# hw2.net
KiCad netlist of a schematic drawn in EAGLE
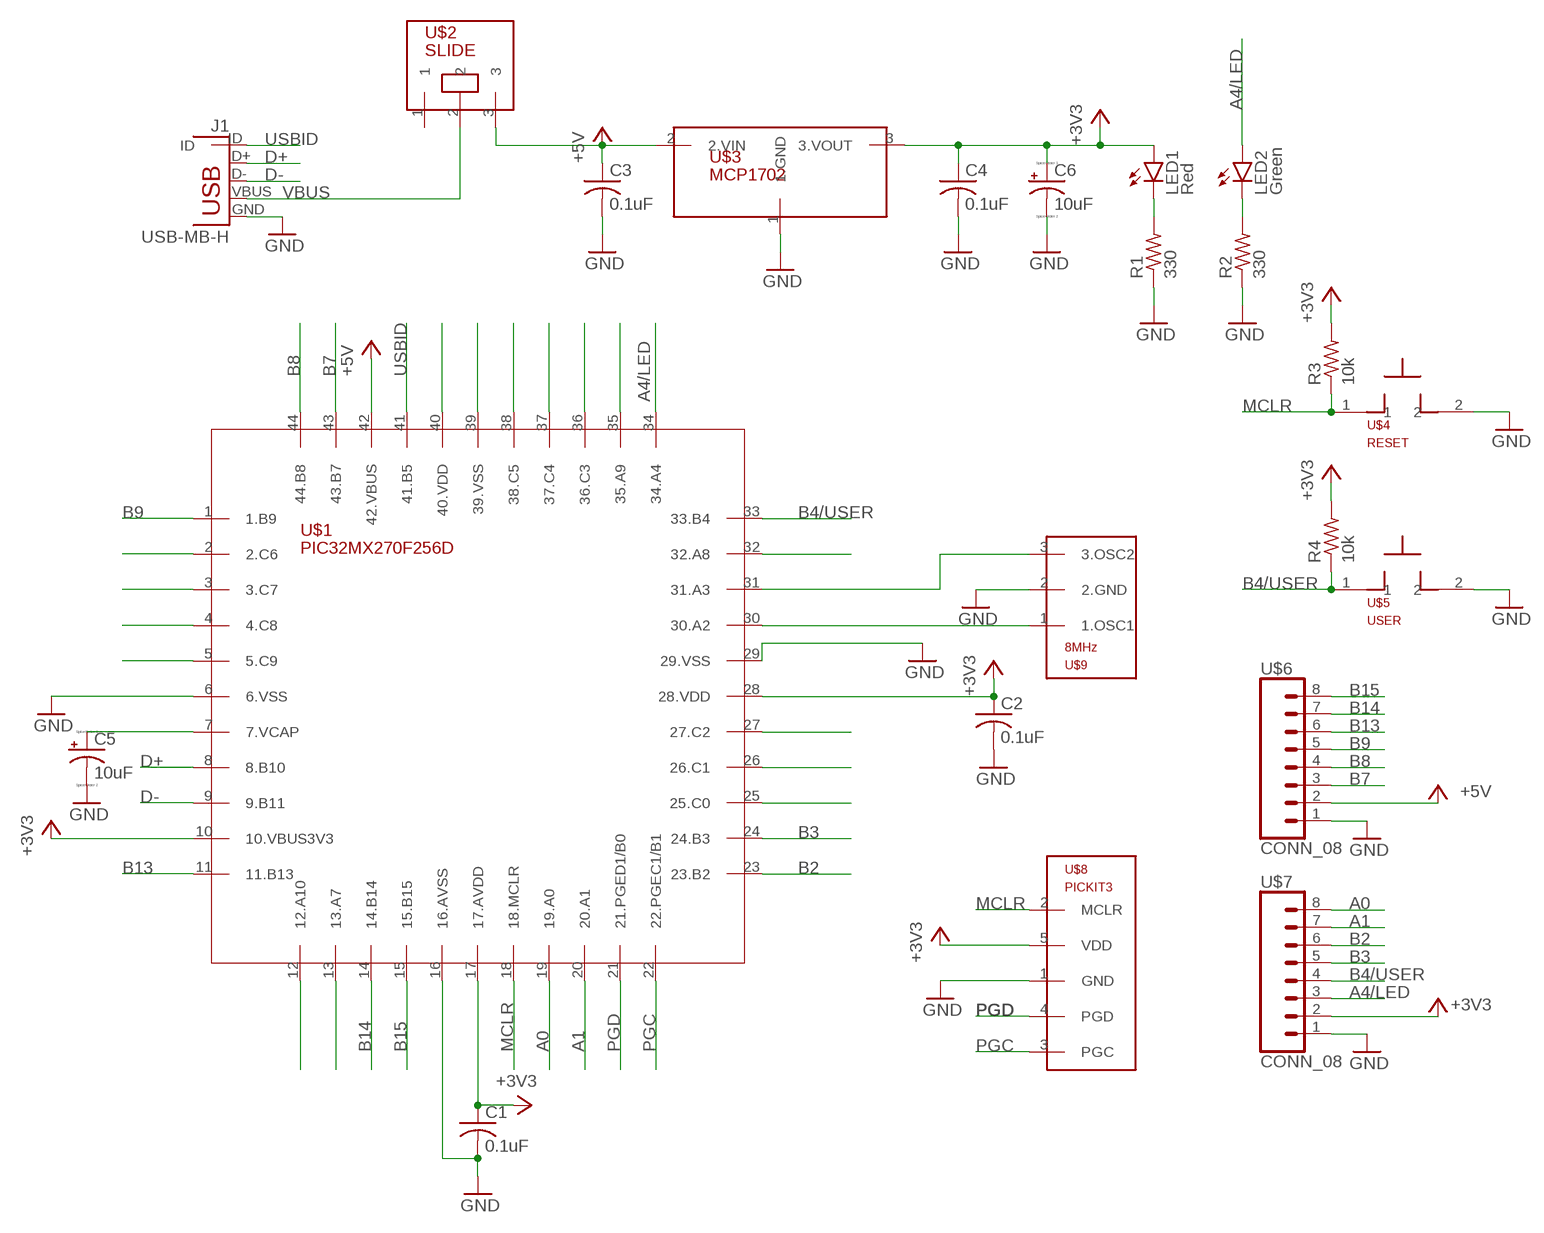
[diagram p0: schematic, sheet 1]

(export (version "E")
  (design (tool "Eeschema 10.0.6"))
  (components
    (comp (ref "C1")
      (value "0.1uF")
      (footprint "eagle-import:C025-025X050")
      (libsource (lib "eagle-import") (part "C-US025-025X050"))
    )
    (comp (ref "C2")
      (value "0.1uF")
      (footprint "eagle-import:C025-025X050")
      (libsource (lib "eagle-import") (part "C-US025-025X050"))
    )
    (comp (ref "C3")
      (value "0.1uF")
      (footprint "eagle-import:C025-025X050")
      (libsource (lib "eagle-import") (part "C-US025-025X050"))
    )
    (comp (ref "C4")
      (value "0.1uF")
      (footprint "eagle-import:C025-025X050")
      (libsource (lib "eagle-import") (part "C-US025-025X050"))
    )
    (comp (ref "C5")
      (value "10uF")
      (footprint "eagle-import:B45181B")
      (libsource (lib "eagle-import") (part "CPOL-USB45181B"))
    )
    (comp (ref "C6")
      (value "10uF")
      (footprint "eagle-import:B45181B")
      (libsource (lib "eagle-import") (part "CPOL-USB45181B"))
    )
    (comp (ref "J1")
      (value "USB-MB-H")
      (footprint "eagle-import:USB-MB-H")
      (libsource (lib "eagle-import") (part "USB-MB-H"))
    )
    (comp (ref "LED1")
      (value "Red")
      (footprint "eagle-import:LED3MM")
      (libsource (lib "eagle-import") (part "LED3MM"))
    )
    (comp (ref "LED2")
      (value "Green")
      (footprint "eagle-import:LED3MM")
      (libsource (lib "eagle-import") (part "LED3MM"))
    )
    (comp (ref "R1")
      (value "330")
      (footprint "eagle-import:0207_10")
      (libsource (lib "eagle-import") (part "R-US_0207/10"))
    )
    (comp (ref "R2")
      (value "330")
      (footprint "eagle-import:0207_10")
      (libsource (lib "eagle-import") (part "R-US_0207/10"))
    )
    (comp (ref "R3")
      (value "10k")
      (footprint "eagle-import:0207_10")
      (libsource (lib "eagle-import") (part "R-US_0207/10"))
    )
    (comp (ref "R4")
      (value "10k")
      (footprint "eagle-import:0207_10")
      (libsource (lib "eagle-import") (part "R-US_0207/10"))
    )
    (comp (ref "U$1")
      (value "PIC32MX270F256D")
      (footprint "eagle-import:TQFP44")
      (libsource (lib "eagle-import") (part "PIC32MX270F256D"))
    )
    (comp (ref "U$2")
      (value "SLIDE")
      (footprint "eagle-import:SLIDE")
      (libsource (lib "eagle-import") (part "SLIDE"))
    )
    (comp (ref "U$3")
      (value "MCP1702")
      (footprint "eagle-import:TO92")
      (libsource (lib "eagle-import") (part "MCP1702"))
    )
    (comp (ref "U$4")
      (value "RESET")
      (footprint "eagle-import:PB")
      (libsource (lib "eagle-import") (part "PB"))
    )
    (comp (ref "U$5")
      (value "USER")
      (footprint "eagle-import:PB")
      (libsource (lib "eagle-import") (part "PB"))
    )
    (comp (ref "U$6")
      (value "CONN_08")
      (footprint "eagle-import:1X08")
      (libsource (lib "eagle-import") (part "CONN_08"))
    )
    (comp (ref "U$7")
      (value "CONN_08")
      (footprint "eagle-import:1X08")
      (libsource (lib "eagle-import") (part "CONN_08"))
    )
    (comp (ref "U$8")
      (value "PICKIT3")
      (footprint "eagle-import:1X05")
      (libsource (lib "eagle-import") (part "PICKIT3"))
    )
    (comp (ref "U$9")
      (value "8MHz")
      (footprint "eagle-import:OSC")
      (libsource (lib "eagle-import") (part "OSC"))
    )
  )
  (nets
    (net (code "1") (name "+3V3") (class "Default")
      (node (ref "C1") (pin "1") (pinfunction "1_1") (pintype "passive"))
      (node (ref "C2") (pin "1") (pinfunction "1_1") (pintype "passive"))
      (node (ref "C4") (pin "1") (pinfunction "1_1") (pintype "passive"))
      (node (ref "C6") (pin "+") (pinfunction "+_+") (pintype "passive"))
      (node (ref "LED1") (pin "A") (pinfunction "A_A") (pintype "passive"))
      (node (ref "R3") (pin "2") (pinfunction "2_2") (pintype "passive"))
      (node (ref "R4") (pin "2") (pinfunction "2_2") (pintype "passive"))
      (node (ref "U$1") (pin "10") (pinfunction "10.VBUS3V3_10") (pintype "bidirectional"))
      (node (ref "U$1") (pin "17") (pinfunction "17.AVDD_17") (pintype "bidirectional"))
      (node (ref "U$1") (pin "28") (pinfunction "28.VDD_28") (pintype "bidirectional"))
      (node (ref "U$3") (pin "3") (pinfunction "3.VOUT_3") (pintype "bidirectional"))
      (node (ref "U$7") (pin "2") (pinfunction "2_2") (pintype "passive"))
      (node (ref "U$8") (pin "5") (pinfunction "VDD_5") (pintype "bidirectional"))
    )
    (net (code "2") (name "+5V") (class "Default")
      (node (ref "C3") (pin "1") (pinfunction "1_1") (pintype "passive"))
      (node (ref "U$1") (pin "42") (pinfunction "42.VBUS_42") (pintype "bidirectional"))
      (node (ref "U$2") (pin "3") (pinfunction "3_3") (pintype "bidirectional"))
      (node (ref "U$3") (pin "2") (pinfunction "2.VIN_2") (pintype "bidirectional"))
      (node (ref "U$6") (pin "2") (pinfunction "2_2") (pintype "passive"))
    )
    (net (code "3") (name "/A0") (class "Default")
      (node (ref "U$1") (pin "19") (pinfunction "19.A0_19") (pintype "bidirectional"))
      (node (ref "U$7") (pin "8") (pinfunction "8_8") (pintype "passive"))
    )
    (net (code "4") (name "/A1") (class "Default")
      (node (ref "U$1") (pin "20") (pinfunction "20.A1_20") (pintype "bidirectional"))
      (node (ref "U$7") (pin "7") (pinfunction "7_7") (pintype "passive"))
    )
    (net (code "5") (name "/A4{slash}LED") (class "Default")
      (node (ref "LED2") (pin "A") (pinfunction "A_A") (pintype "passive"))
      (node (ref "U$1") (pin "34") (pinfunction "34.A4_34") (pintype "bidirectional"))
      (node (ref "U$7") (pin "3") (pinfunction "3_3") (pintype "passive"))
    )
    (net (code "6") (name "/B2") (class "Default")
      (node (ref "U$1") (pin "23") (pinfunction "23.B2_23") (pintype "bidirectional"))
      (node (ref "U$7") (pin "6") (pinfunction "6_6") (pintype "passive"))
    )
    (net (code "7") (name "/B3") (class "Default")
      (node (ref "U$1") (pin "24") (pinfunction "24.B3_24") (pintype "bidirectional"))
      (node (ref "U$7") (pin "5") (pinfunction "5_5") (pintype "passive"))
    )
    (net (code "8") (name "/B4{slash}USER") (class "Default")
      (node (ref "R4") (pin "1") (pinfunction "1_1") (pintype "passive"))
      (node (ref "U$1") (pin "33") (pinfunction "33.B4_33") (pintype "bidirectional"))
      (node (ref "U$5") (pin "1") (pinfunction "1_1") (pintype "bidirectional"))
      (node (ref "U$7") (pin "4") (pinfunction "4_4") (pintype "passive"))
    )
    (net (code "9") (name "/B7") (class "Default")
      (node (ref "U$1") (pin "43") (pinfunction "43.B7_43") (pintype "bidirectional"))
      (node (ref "U$6") (pin "3") (pinfunction "3_3") (pintype "passive"))
    )
    (net (code "10") (name "/B8") (class "Default")
      (node (ref "U$1") (pin "44") (pinfunction "44.B8_44") (pintype "bidirectional"))
      (node (ref "U$6") (pin "4") (pinfunction "4_4") (pintype "passive"))
    )
    (net (code "11") (name "/B9") (class "Default")
      (node (ref "U$1") (pin "1") (pinfunction "1.B9_1") (pintype "bidirectional"))
      (node (ref "U$6") (pin "5") (pinfunction "5_5") (pintype "passive"))
    )
    (net (code "12") (name "/B13") (class "Default")
      (node (ref "U$1") (pin "11") (pinfunction "11.B13_11") (pintype "bidirectional"))
      (node (ref "U$6") (pin "6") (pinfunction "6_6") (pintype "passive"))
    )
    (net (code "13") (name "/B14") (class "Default")
      (node (ref "U$1") (pin "14") (pinfunction "14.B14_14") (pintype "bidirectional"))
      (node (ref "U$6") (pin "7") (pinfunction "7_7") (pintype "passive"))
    )
    (net (code "14") (name "/B15") (class "Default")
      (node (ref "U$1") (pin "15") (pinfunction "15.B15_15") (pintype "bidirectional"))
      (node (ref "U$6") (pin "8") (pinfunction "8_8") (pintype "passive"))
    )
    (net (code "15") (name "/D+") (class "Default")
      (node (ref "J1") (pin "D+") (pinfunction "D+_D+") (pintype "bidirectional"))
      (node (ref "U$1") (pin "8") (pinfunction "8.B10_8") (pintype "bidirectional"))
    )
    (net (code "16") (name "/D-") (class "Default")
      (node (ref "J1") (pin "D-") (pinfunction "D-_D-") (pintype "bidirectional"))
      (node (ref "U$1") (pin "9") (pinfunction "9.B11_9") (pintype "bidirectional"))
    )
    (net (code "17") (name "/MCLR") (class "Default")
      (node (ref "R3") (pin "1") (pinfunction "1_1") (pintype "passive"))
      (node (ref "U$1") (pin "18") (pinfunction "18.MCLR_18") (pintype "bidirectional"))
      (node (ref "U$4") (pin "1") (pinfunction "1_1") (pintype "bidirectional"))
      (node (ref "U$8") (pin "2") (pinfunction "MCLR_2") (pintype "bidirectional"))
    )
    (net (code "18") (name "/PGC") (class "Default")
      (node (ref "U$1") (pin "22") (pinfunction "22.PGEC1/B1_22") (pintype "bidirectional"))
      (node (ref "U$8") (pin "3") (pinfunction "PGC_3") (pintype "bidirectional"))
    )
    (net (code "19") (name "/PGD") (class "Default")
      (node (ref "U$1") (pin "21") (pinfunction "21.PGED1/B0_21") (pintype "bidirectional"))
      (node (ref "U$8") (pin "4") (pinfunction "PGD_4") (pintype "bidirectional"))
    )
    (net (code "20") (name "/USBID") (class "Default")
      (node (ref "J1") (pin "ID") (pinfunction "ID_ID") (pintype "bidirectional"))
      (node (ref "U$1") (pin "41") (pinfunction "41.B5_41") (pintype "bidirectional"))
    )
    (net (code "21") (name "/VBUS") (class "Default")
      (node (ref "J1") (pin "VBUS") (pinfunction "VBUS_VBUS") (pintype "bidirectional"))
      (node (ref "U$2") (pin "2") (pinfunction "2_2") (pintype "bidirectional"))
    )
    (net (code "22") (name "GND") (class "Default")
      (node (ref "C1") (pin "2") (pinfunction "2_2") (pintype "passive"))
      (node (ref "C2") (pin "2") (pinfunction "2_2") (pintype "passive"))
      (node (ref "C3") (pin "2") (pinfunction "2_2") (pintype "passive"))
      (node (ref "C4") (pin "2") (pinfunction "2_2") (pintype "passive"))
      (node (ref "C5") (pin "-") (pinfunction "-_-") (pintype "passive"))
      (node (ref "C6") (pin "-") (pinfunction "-_-") (pintype "passive"))
      (node (ref "J1") (pin "GND") (pinfunction "GND_GND") (pintype "bidirectional"))
      (node (ref "R1") (pin "1") (pinfunction "1_1") (pintype "passive"))
      (node (ref "R2") (pin "1") (pinfunction "1_1") (pintype "passive"))
      (node (ref "U$1") (pin "16") (pinfunction "16.AVSS_16") (pintype "bidirectional"))
      (node (ref "U$1") (pin "29") (pinfunction "29.VSS_29") (pintype "bidirectional"))
      (node (ref "U$1") (pin "6") (pinfunction "6.VSS_6") (pintype "bidirectional"))
      (node (ref "U$3") (pin "1") (pinfunction "1.GND_1") (pintype "bidirectional"))
      (node (ref "U$4") (pin "2") (pinfunction "2_2") (pintype "bidirectional"))
      (node (ref "U$5") (pin "2") (pinfunction "2_2") (pintype "bidirectional"))
      (node (ref "U$6") (pin "1") (pinfunction "1_1") (pintype "passive"))
      (node (ref "U$7") (pin "1") (pinfunction "1_1") (pintype "passive"))
      (node (ref "U$8") (pin "1") (pinfunction "GND_1") (pintype "bidirectional"))
      (node (ref "U$9") (pin "2") (pinfunction "2.GND_2") (pintype "bidirectional"))
    )
    (net (code "23") (name "Net-(LED1-C)") (class "Default")
      (node (ref "LED1") (pin "K") (pinfunction "C_K") (pintype "passive"))
      (node (ref "R1") (pin "2") (pinfunction "2_2") (pintype "passive"))
    )
    (net (code "24") (name "Net-(LED2-C)") (class "Default")
      (node (ref "LED2") (pin "K") (pinfunction "C_K") (pintype "passive"))
      (node (ref "R2") (pin "2") (pinfunction "2_2") (pintype "passive"))
    )
    (net (code "25") (name "Net-(U$1-7.VCAP)") (class "Default")
      (node (ref "C5") (pin "+") (pinfunction "+_+") (pintype "passive"))
      (node (ref "U$1") (pin "7") (pinfunction "7.VCAP_7") (pintype "bidirectional"))
    )
    (net (code "26") (name "Net-(U$1-30.A2)") (class "Default")
      (node (ref "U$1") (pin "30") (pinfunction "30.A2_30") (pintype "bidirectional"))
      (node (ref "U$9") (pin "1") (pinfunction "1.OSC1_1") (pintype "bidirectional"))
    )
    (net (code "27") (name "Net-(U$1-31.A3)") (class "Default")
      (node (ref "U$1") (pin "31") (pinfunction "31.A3_31") (pintype "bidirectional"))
      (node (ref "U$9") (pin "3") (pinfunction "3.OSC2_3") (pintype "bidirectional"))
    )
    (net (code "28") (name "unconnected-(U$1-2.C6-Pad2)") (class "Default")
      (node (ref "U$1") (pin "2") (pinfunction "2.C6_2") (pintype "bidirectional"))
    )
    (net (code "29") (name "unconnected-(U$1-3.C7-Pad3)") (class "Default")
      (node (ref "U$1") (pin "3") (pinfunction "3.C7_3") (pintype "bidirectional"))
    )
    (net (code "30") (name "unconnected-(U$1-4.C8-Pad4)") (class "Default")
      (node (ref "U$1") (pin "4") (pinfunction "4.C8_4") (pintype "bidirectional"))
    )
    (net (code "31") (name "unconnected-(U$1-5.C9-Pad5)") (class "Default")
      (node (ref "U$1") (pin "5") (pinfunction "5.C9_5") (pintype "bidirectional"))
    )
    (net (code "32") (name "unconnected-(U$1-12.A10-Pad12)") (class "Default")
      (node (ref "U$1") (pin "12") (pinfunction "12.A10_12") (pintype "bidirectional"))
    )
    (net (code "33") (name "unconnected-(U$1-13.A7-Pad13)") (class "Default")
      (node (ref "U$1") (pin "13") (pinfunction "13.A7_13") (pintype "bidirectional"))
    )
    (net (code "34") (name "unconnected-(U$1-25.C0-Pad25)") (class "Default")
      (node (ref "U$1") (pin "25") (pinfunction "25.C0_25") (pintype "bidirectional"))
    )
    (net (code "35") (name "unconnected-(U$1-26.C1-Pad26)") (class "Default")
      (node (ref "U$1") (pin "26") (pinfunction "26.C1_26") (pintype "bidirectional"))
    )
    (net (code "36") (name "unconnected-(U$1-27.C2-Pad27)") (class "Default")
      (node (ref "U$1") (pin "27") (pinfunction "27.C2_27") (pintype "bidirectional"))
    )
    (net (code "37") (name "unconnected-(U$1-32.A8-Pad32)") (class "Default")
      (node (ref "U$1") (pin "32") (pinfunction "32.A8_32") (pintype "bidirectional"))
    )
    (net (code "38") (name "unconnected-(U$1-35.A9-Pad35)") (class "Default")
      (node (ref "U$1") (pin "35") (pinfunction "35.A9_35") (pintype "bidirectional"))
    )
    (net (code "39") (name "unconnected-(U$1-36.C3-Pad36)") (class "Default")
      (node (ref "U$1") (pin "36") (pinfunction "36.C3_36") (pintype "bidirectional"))
    )
    (net (code "40") (name "unconnected-(U$1-37.C4-Pad37)") (class "Default")
      (node (ref "U$1") (pin "37") (pinfunction "37.C4_37") (pintype "bidirectional"))
    )
    (net (code "41") (name "unconnected-(U$1-38.C5-Pad38)") (class "Default")
      (node (ref "U$1") (pin "38") (pinfunction "38.C5_38") (pintype "bidirectional"))
    )
    (net (code "42") (name "unconnected-(U$1-39.VSS-Pad39)") (class "Default")
      (node (ref "U$1") (pin "39") (pinfunction "39.VSS_39") (pintype "bidirectional"))
    )
    (net (code "43") (name "unconnected-(U$1-40.VDD-Pad40)") (class "Default")
      (node (ref "U$1") (pin "40") (pinfunction "40.VDD_40") (pintype "bidirectional"))
    )
    (net (code "44") (name "unconnected-(U$2-Pad1)") (class "Default")
      (node (ref "U$2") (pin "1") (pinfunction "1_1") (pintype "bidirectional"))
    )
  )
)
